# OpenTx_NucleoF412zg.net
KiCad netlist of a schematic drawn in Altium Designer
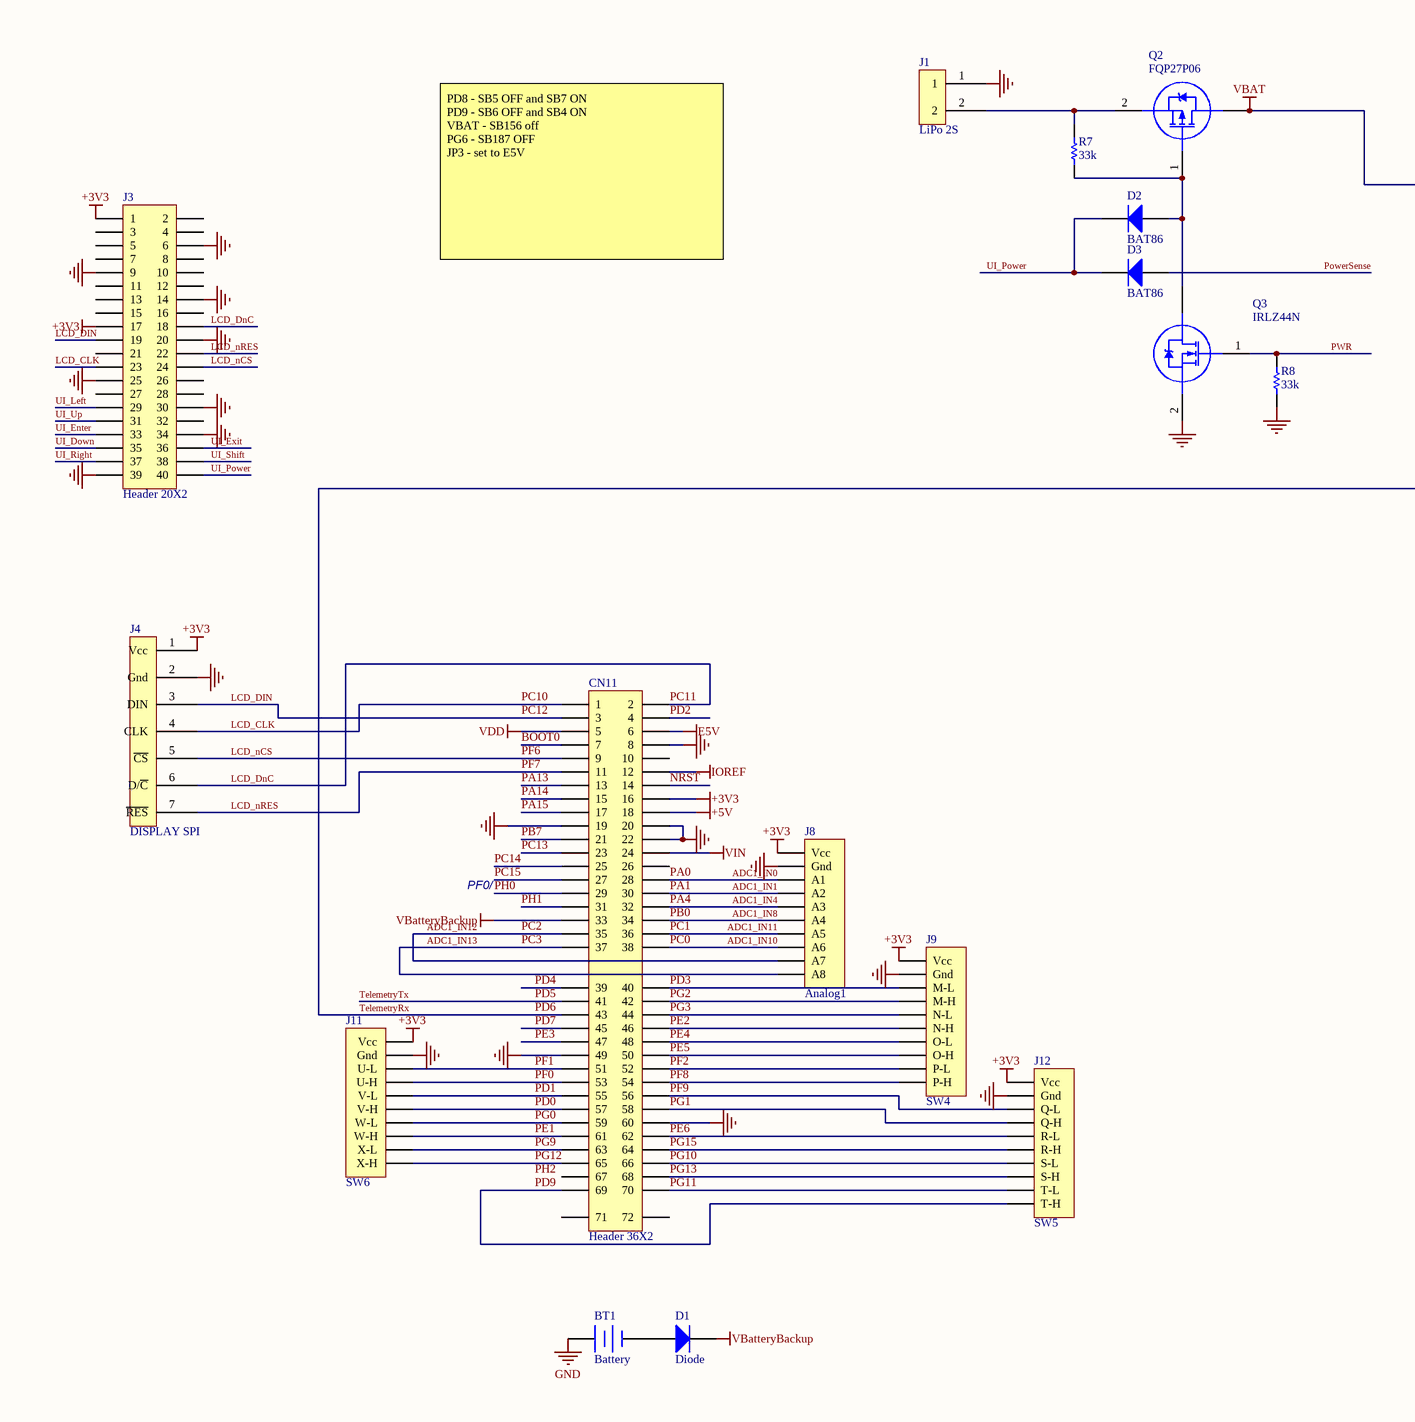
[diagram p0: OpenTx_NucleoF412zg.SchDoc, left]
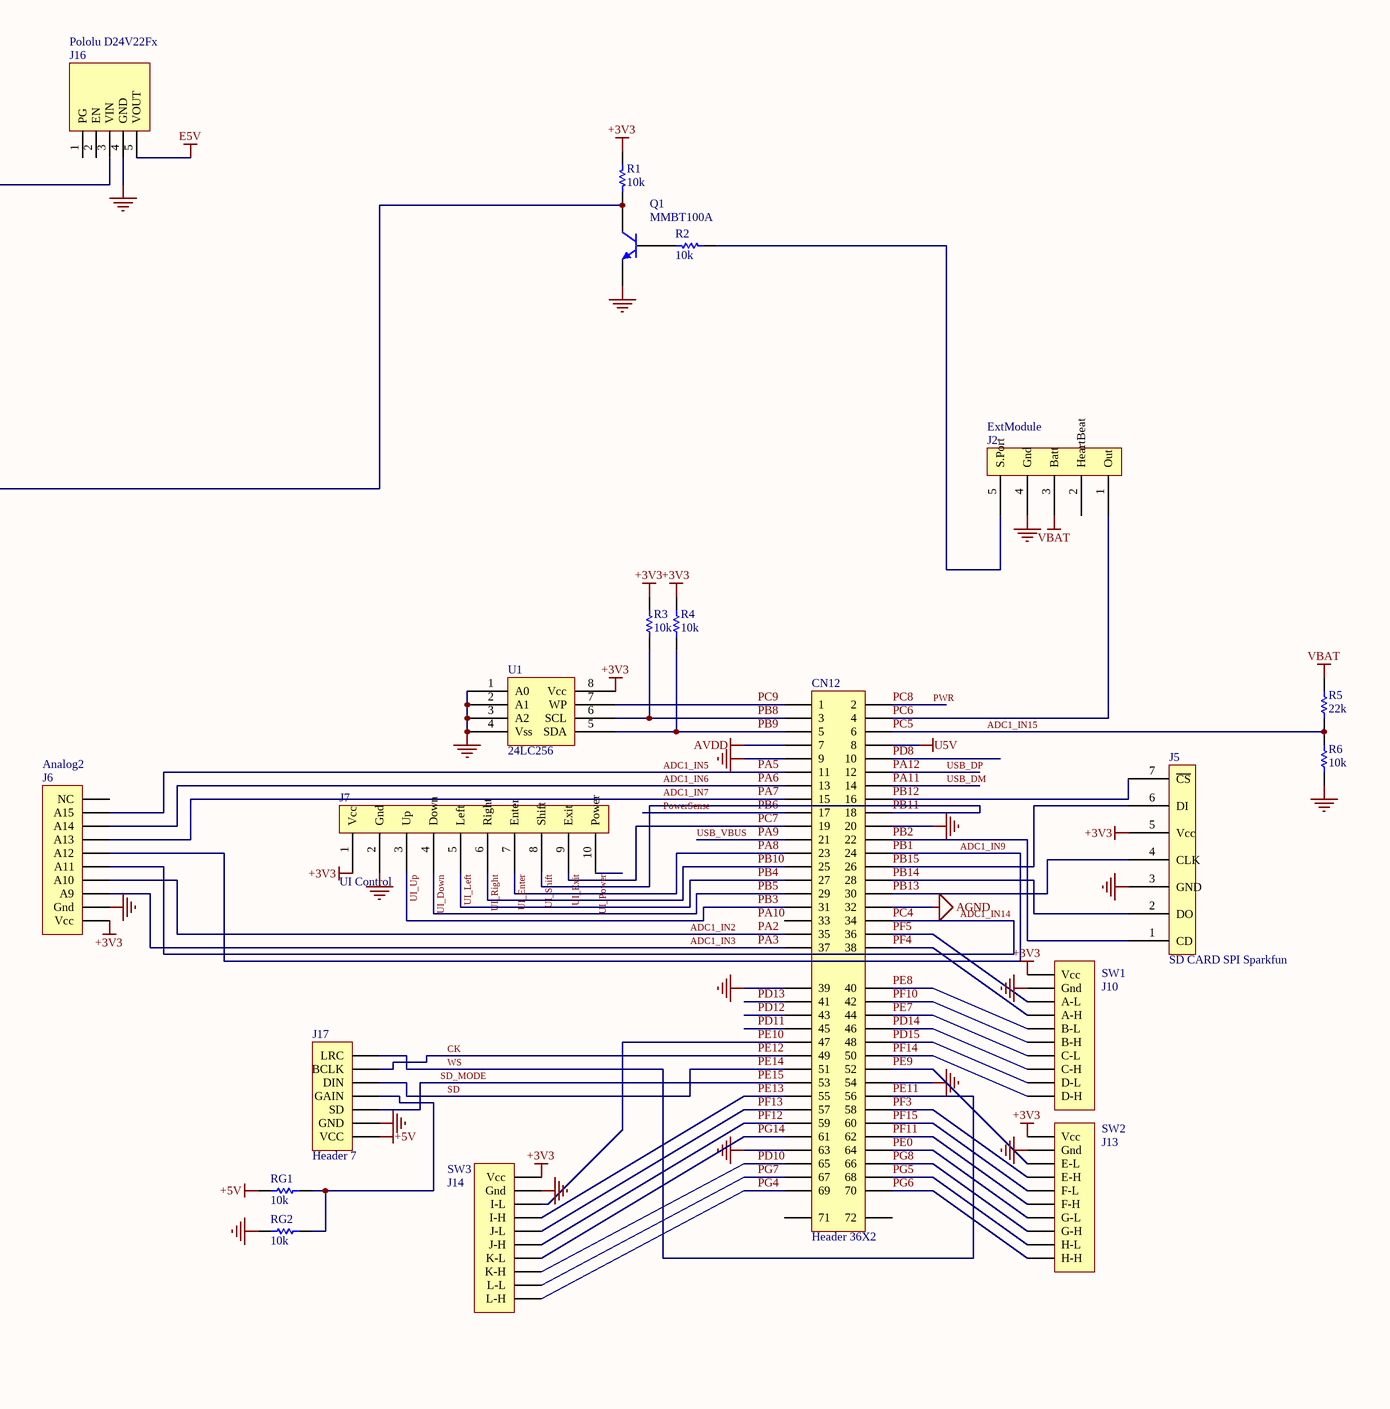
[diagram p1: OpenTx_NucleoF412zg.SchDoc, right]

(export (version "E")
  (design (tool "Eeschema 10.0.6"))
  (components
    (comp (ref "BT1")
      (value "Battery")
      (footprint "Button Cell Holder 20mm")
      (description "Multicell Battery")
      (fields (field (name "PUBLISHER") "Altium Limited"))
      (libsource (lib "Miscellaneous Devices") (part "Battery"))
    )
    (comp (ref "CN11")
      (value "Header 36X2")
      (footprint "HDR35x2 Bottom")
      (description "Header, 36-Pin, Dual row")
      (fields (field (name "PUBLISHER") "Altium Limited"))
      (libsource (lib "MB1137") (part "Header 36X2"))
    )
    (comp (ref "CN12")
      (value "Header 36X2")
      (footprint "HDR35x2 Bottom")
      (description "Header, 36-Pin, Dual row")
      (fields (field (name "PUBLISHER") "Altium Limited"))
      (libsource (lib "MB1137") (part "Header 36X2"))
    )
    (comp (ref "D1")
      (value "Diode")
      (footprint "DO-35 400")
      (fields (field (name "PUBLISHER") "Altium Limited"))
      (libsource (lib "Custom") (part "Diode"))
    )
    (comp (ref "D2")
      (value "BAT86")
      (footprint "DO-35 200")
      (description "Diode")
      (fields (field (name "PUBLISHER") "Altium Limited"))
      (libsource (lib "Custom") (part "Diode"))
    )
    (comp (ref "D3")
      (value "BAT86")
      (footprint "DO-35 200")
      (description "Diode")
      (fields (field (name "PUBLISHER") "Altium Limited"))
      (libsource (lib "Custom") (part "Diode"))
    )
    (comp (ref "J1")
      (value "LiPo 2S")
      (footprint "0.1 SIP 2 PIN")
      (libsource (lib "Custom") (part "SIP2 CONNECTOR"))
    )
    (comp (ref "J2")
      (value "ExtModule")
      (footprint "0.1 SIP 5 PIN")
      (libsource (lib "Custom") (part "SIP5 CONNECTOR"))
    )
    (comp (ref "J3")
      (value "Header 20X2")
      (footprint "HDR20x2 Shrouded")
      (description "Header, 20-Pin, Dual row")
      (fields (field (name "PUBLISHER") "Altium Limited"))
      (libsource (lib "Miscellaneous Connectors") (part "Header 20X2"))
    )
    (comp (ref "J4")
      (value "DISPLAY SPI")
      (footprint "0.1 SIP 8 PIN")
      (libsource (lib "") (part "SIP7 CONNECTOR_1"))
    )
    (comp (ref "J5")
      (value "SD CARD SPI Sparkfun")
      (footprint "Sparkfun SD Card")
      (libsource (lib "Custom") (part "SIP7 CONNECTOR"))
    )
    (comp (ref "J6")
      (value "Analog2")
      (footprint "0.1 SIP 10 PIN")
      (description "Header, 10-Pin")
      (fields (field (name "PUBLISHER") "Altium Limited"))
      (libsource (lib "") (part "Header 10_6"))
    )
    (comp (ref "J7")
      (value "UI Control")
      (footprint "0.1 SIP 10 PIN")
      (libsource (lib "Custom") (part "SIP10 CONNECTOR"))
    )
    (comp (ref "J8")
      (value "Analog1")
      (footprint "0.1 SIP 10 PIN")
      (description "Header, 10-Pin")
      (fields (field (name "PUBLISHER") "Altium Limited"))
      (libsource (lib "") (part "Header 10_2"))
    )
    (comp (ref "J9")
      (value "SW4")
      (footprint "0.1 SIP 10 PIN")
      (description "Header, 10-Pin")
      (fields (field (name "PUBLISHER") "Altium Limited"))
      (libsource (lib "") (part "Header 10_4"))
    )
    (comp (ref "J10")
      (value "SW1")
      (footprint "0.1 SIP 10 PIN")
      (description "Header, 10-Pin")
      (fields (field (name "PUBLISHER") "Altium Limited"))
      (libsource (lib "") (part "Header 10_3"))
    )
    (comp (ref "J11")
      (value "SW6")
      (footprint "0.1 SIP 10 PIN")
      (description "Header, 10-Pin")
      (fields (field (name "PUBLISHER") "Altium Limited"))
      (libsource (lib "") (part "Header 10_1"))
    )
    (comp (ref "J12")
      (value "SW5")
      (footprint "0.1 SIP 10 PIN")
      (description "Header, 10-Pin")
      (fields (field (name "PUBLISHER") "Altium Limited"))
      (libsource (lib "Miscellaneous Connectors") (part "Header 10"))
    )
    (comp (ref "J13")
      (value "SW2")
      (footprint "0.1 SIP 10 PIN")
      (description "Header, 10-Pin")
      (fields (field (name "PUBLISHER") "Altium Limited"))
      (libsource (lib "") (part "Header 10_5"))
    )
    (comp (ref "J14")
      (value "SW3")
      (footprint "0.1 SIP 10 PIN")
      (description "Header, 10-Pin")
      (fields (field (name "PUBLISHER") "Altium Limited"))
      (libsource (lib "") (part "Header 10_1"))
    )
    (comp (ref "J16")
      (value "Pololu D24V22Fx")
      (footprint "Pololu D24V22Fx")
      (libsource (lib "Custom") (part "Pololu D24V22Fx"))
    )
    (comp (ref "J17")
      (value "Header 7")
      (footprint "ADAFruit I2S MAX98357A")
      (description "Header, 7-Pin")
      (fields (field (name "PUBLISHER") "Altium Limited"))
      (libsource (lib "Miscellaneous Connectors") (part "Header 7"))
    )
    (comp (ref "Q1")
      (value "MMBT100A")
      (footprint "TO-92 0.1\"")
      (description "General Purpose Amplifier NPN Silicon")
      (fields (field (name "PUBLISHER") "Altium Limited"))
      (libsource (lib "Custom") (part "MMBT100A"))
    )
    (comp (ref "Q2")
      (value "FQP27P06")
      (footprint "TO-220")
      (description "HEXFET Power MOSFET")
      (fields (field (name "PUBLISHER") "Altium Limited"))
      (libsource (lib "Custom") (part "NTR4101P"))
    )
    (comp (ref "Q3")
      (value "IRLZ44N")
      (footprint "TO-220")
      (description "HEXFET Power MOSFET")
      (fields (field (name "PUBLISHER") "Altium Limited"))
      (libsource (lib "Custom") (part "NTR4501N"))
    )
    (comp (ref "R1")
      (value "10k")
      (footprint "Resistor Axial 1/8W 0.4")
      (fields (field (name "Comment") "Res1"))
      (libsource (lib "Custom") (part "Resistor"))
    )
    (comp (ref "R2")
      (value "10k")
      (footprint "Resistor Axial 1/8W 0.4")
      (fields (field (name "Comment") "Res1"))
      (libsource (lib "Custom") (part "Resistor"))
    )
    (comp (ref "R3")
      (value "10k")
      (footprint "Resistor Axial 1/8W 0.4")
      (fields (field (name "Comment") "Res1"))
      (libsource (lib "Custom") (part "Resistor"))
    )
    (comp (ref "R4")
      (value "10k")
      (footprint "Resistor Axial 1/8W 0.4")
      (fields (field (name "Comment") "Res1"))
      (libsource (lib "Custom") (part "Resistor"))
    )
    (comp (ref "R5")
      (value "22k")
      (footprint "Resistor Axial 1/8W 0.4")
      (fields (field (name "Comment") "Res1"))
      (libsource (lib "Custom") (part "Resistor"))
    )
    (comp (ref "R6")
      (value "10k")
      (footprint "Resistor Axial 1/8W 0.4")
      (fields (field (name "Comment") "Res1"))
      (libsource (lib "Custom") (part "Resistor"))
    )
    (comp (ref "R7")
      (value "33k")
      (footprint "Resistor Axial 1/8W 0.4")
      (fields (field (name "Comment") "Res1"))
      (libsource (lib "Custom") (part "Resistor"))
    )
    (comp (ref "R8")
      (value "33k")
      (footprint "Resistor Axial 1/8W 0.4")
      (fields (field (name "Comment") "Res1"))
      (libsource (lib "Custom") (part "Resistor"))
    )
    (comp (ref "RG1")
      (value "10k")
      (footprint "Resistor Axial 1/8W 0.4")
      (fields (field (name "Comment") "Res1"))
      (libsource (lib "Custom") (part "Resistor"))
    )
    (comp (ref "RG2")
      (value "10k")
      (footprint "Resistor Axial 1/8W 0.4")
      (fields (field (name "Comment") "Res1"))
      (libsource (lib "Custom") (part "Resistor"))
    )
    (comp (ref "U1") (value "24LC256") (footprint "DIP8") (libsource (lib "Custom") (part "24LC256")))
  )
  (nets
    (net (code "1") (name "+3V3") (class "Default")
      (node (ref "CN11") (pin "16") (pinfunction "16_16") (pintype "passive"))
      (node (ref "J10") (pin "1") (pinfunction "Vcc_1") (pintype "passive"))
      (node (ref "J11") (pin "1") (pinfunction "Vcc_1") (pintype "passive"))
      (node (ref "J12") (pin "1") (pinfunction "Vcc_1") (pintype "passive"))
      (node (ref "J13") (pin "1") (pinfunction "Vcc_1") (pintype "passive"))
      (node (ref "J14") (pin "1") (pinfunction "Vcc_1") (pintype "passive"))
      (node (ref "J3") (pin "1") (pinfunction "1_1") (pintype "passive"))
      (node (ref "J3") (pin "17") (pinfunction "17_17") (pintype "passive"))
      (node (ref "J4") (pin "1") (pinfunction "Vcc_1") (pintype "passive"))
      (node (ref "J5") (pin "5") (pinfunction "Vcc_5") (pintype "passive"))
      (node (ref "J6") (pin "1") (pinfunction "Vcc_1") (pintype "passive"))
      (node (ref "J7") (pin "1") (pinfunction "Vcc_1") (pintype "passive"))
      (node (ref "J8") (pin "1") (pinfunction "Vcc_1") (pintype "passive"))
      (node (ref "J9") (pin "1") (pinfunction "Vcc_1") (pintype "passive"))
      (node (ref "R1") (pin "1") (pinfunction "1_1") (pintype "passive"))
      (node (ref "R3") (pin "1") (pinfunction "1_1") (pintype "passive"))
      (node (ref "R4") (pin "1") (pinfunction "1_1") (pintype "passive"))
      (node (ref "U1") (pin "8") (pinfunction "Vcc_8") (pintype "passive"))
    )
    (net (code "2") (name "+5V") (class "Default")
      (node (ref "CN11") (pin "18") (pinfunction "18_18") (pintype "passive"))
      (node (ref "J17") (pin "7") (pinfunction "VCC_7") (pintype "passive"))
      (node (ref "RG1") (pin "1") (pinfunction "1_1") (pintype "passive"))
    )
    (net (code "3") (name "/ADC1_IN0") (class "Default")
      (node (ref "CN11") (pin "28") (pinfunction "28_28") (pintype "passive"))
      (node (ref "J8") (pin "3") (pinfunction "A1_3") (pintype "passive"))
    )
    (net (code "4") (name "/ADC1_IN1") (class "Default")
      (node (ref "CN11") (pin "30") (pinfunction "30_30") (pintype "passive"))
      (node (ref "J8") (pin "4") (pinfunction "A2_4") (pintype "passive"))
    )
    (net (code "5") (name "/ADC1_IN2") (class "Default")
      (node (ref "CN12") (pin "35") (pinfunction "35_35") (pintype "passive"))
      (node (ref "J6") (pin "4") (pinfunction "A10_4") (pintype "passive"))
    )
    (net (code "6") (name "/ADC1_IN3") (class "Default")
      (node (ref "CN12") (pin "37") (pinfunction "37_37") (pintype "passive"))
      (node (ref "J6") (pin "3") (pinfunction "A9_3") (pintype "passive"))
    )
    (net (code "7") (name "/ADC1_IN4") (class "Default")
      (node (ref "CN11") (pin "32") (pinfunction "32_32") (pintype "passive"))
      (node (ref "J8") (pin "5") (pinfunction "A3_5") (pintype "passive"))
    )
    (net (code "8") (name "/ADC1_IN5") (class "Default")
      (node (ref "CN12") (pin "11") (pinfunction "11_11") (pintype "passive"))
      (node (ref "J6") (pin "9") (pinfunction "A15_9") (pintype "passive"))
    )
    (net (code "9") (name "/ADC1_IN6") (class "Default")
      (node (ref "CN12") (pin "13") (pinfunction "13_13") (pintype "passive"))
      (node (ref "J6") (pin "8") (pinfunction "A14_8") (pintype "passive"))
    )
    (net (code "10") (name "/ADC1_IN7") (class "Default")
      (node (ref "CN12") (pin "15") (pinfunction "15_15") (pintype "passive"))
      (node (ref "J6") (pin "7") (pinfunction "A13_7") (pintype "passive"))
    )
    (net (code "11") (name "/ADC1_IN8") (class "Default")
      (node (ref "CN11") (pin "34") (pinfunction "34_34") (pintype "passive"))
      (node (ref "J8") (pin "6") (pinfunction "A4_6") (pintype "passive"))
    )
    (net (code "12") (name "/ADC1_IN9") (class "Default")
      (node (ref "CN12") (pin "24") (pinfunction "24_24") (pintype "passive"))
      (node (ref "J6") (pin "6") (pinfunction "A12_6") (pintype "passive"))
    )
    (net (code "13") (name "/ADC1_IN10") (class "Default")
      (node (ref "CN11") (pin "38") (pinfunction "38_38") (pintype "passive"))
      (node (ref "J8") (pin "8") (pinfunction "A6_8") (pintype "passive"))
    )
    (net (code "14") (name "/ADC1_IN11") (class "Default")
      (node (ref "CN11") (pin "36") (pinfunction "36_36") (pintype "passive"))
      (node (ref "J8") (pin "7") (pinfunction "A5_7") (pintype "passive"))
    )
    (net (code "15") (name "/ADC1_IN12") (class "Default")
      (node (ref "CN11") (pin "35") (pinfunction "35_35") (pintype "passive"))
      (node (ref "J8") (pin "9") (pinfunction "A7_9") (pintype "passive"))
    )
    (net (code "16") (name "/ADC1_IN13") (class "Default")
      (node (ref "CN11") (pin "37") (pinfunction "37_37") (pintype "passive"))
      (node (ref "J8") (pin "10") (pinfunction "A8_10") (pintype "passive"))
    )
    (net (code "17") (name "/ADC1_IN14") (class "Default")
      (node (ref "CN12") (pin "34") (pinfunction "34_34") (pintype "passive"))
      (node (ref "J6") (pin "5") (pinfunction "A11_5") (pintype "passive"))
    )
    (net (code "18") (name "/ADC1_IN15") (class "Default")
      (node (ref "CN12") (pin "6") (pinfunction "6_6") (pintype "passive"))
      (node (ref "R5") (pin "2") (pinfunction "2_2") (pintype "passive"))
      (node (ref "R6") (pin "1") (pinfunction "1_1") (pintype "passive"))
    )
    (net (code "19") (name "/BOOT0") (class "Default")
      (node (ref "CN11") (pin "7") (pinfunction "7_7") (pintype "passive"))
    )
    (net (code "20") (name "/CK") (class "Default")
      (node (ref "CN12") (pin "49") (pinfunction "49_49") (pintype "passive"))
      (node (ref "J17") (pin "2") (pinfunction "BCLK_2") (pintype "passive"))
    )
    (net (code "21") (name "/LCD_CLK") (class "Default")
      (node (ref "CN11") (pin "1") (pinfunction "1_1") (pintype "passive"))
      (node (ref "J3") (pin "23") (pinfunction "23_23") (pintype "passive"))
      (node (ref "J4") (pin "4") (pinfunction "CLK_4") (pintype "passive"))
    )
    (net (code "22") (name "/LCD_DIN") (class "Default")
      (node (ref "CN11") (pin "3") (pinfunction "3_3") (pintype "passive"))
      (node (ref "J3") (pin "19") (pinfunction "19_19") (pintype "passive"))
      (node (ref "J4") (pin "3") (pinfunction "DIN_3") (pintype "passive"))
    )
    (net (code "23") (name "/LCD_DnC") (class "Default")
      (node (ref "CN11") (pin "2") (pinfunction "2_2") (pintype "passive"))
      (node (ref "J3") (pin "18") (pinfunction "18_18") (pintype "passive"))
      (node (ref "J4") (pin "6") (pinfunction "D/~{C}_6") (pintype "passive"))
    )
    (net (code "24") (name "/LCD_nCS") (class "Default")
      (node (ref "CN11") (pin "9") (pinfunction "9_9") (pintype "passive"))
      (node (ref "J3") (pin "24") (pinfunction "24_24") (pintype "passive"))
      (node (ref "J4") (pin "5") (pinfunction "~{CS}_5") (pintype "passive"))
    )
    (net (code "25") (name "/LCD_nRES") (class "Default")
      (node (ref "CN11") (pin "11") (pinfunction "11_11") (pintype "passive"))
      (node (ref "J3") (pin "22") (pinfunction "22_22") (pintype "passive"))
      (node (ref "J4") (pin "7") (pinfunction "~{RES}_7") (pintype "passive"))
    )
    (net (code "26") (name "/NRST") (class "Default")
      (node (ref "CN11") (pin "14") (pinfunction "14_14") (pintype "passive"))
    )
    (net (code "27") (name "/PA8") (class "Default")
      (node (ref "CN12") (pin "23") (pinfunction "23_23") (pintype "passive"))
      (node (ref "J3") (pin "33") (pinfunction "33_33") (pintype "passive"))
      (node (ref "J7") (pin "7") (pinfunction "Enter_7") (pintype "passive"))
    )
    (net (code "28") (name "/PA9") (class "Default")
      (node (ref "CN12") (pin "21") (pinfunction "21_21") (pintype "passive"))
    )
    (net (code "30") (name "/PA11") (class "Default")
      (node (ref "CN12") (pin "14") (pinfunction "14_14") (pintype "passive"))
    )
    (net (code "31") (name "/PA12") (class "Default")
      (node (ref "CN12") (pin "12") (pinfunction "12_12") (pintype "passive"))
    )
    (net (code "32") (name "/PA13") (class "Default")
      (node (ref "CN11") (pin "13") (pinfunction "13_13") (pintype "passive"))
    )
    (net (code "33") (name "/PA14") (class "Default")
      (node (ref "CN11") (pin "15") (pinfunction "15_15") (pintype "passive"))
    )
    (net (code "34") (name "/PA15") (class "Default")
      (node (ref "CN11") (pin "17") (pinfunction "17_17") (pintype "passive"))
    )
    (net (code "35") (name "/PB2") (class "Default")
      (node (ref "CN12") (pin "22") (pinfunction "22_22") (pintype "passive"))
      (node (ref "J5") (pin "1") (pinfunction "CD_1") (pintype "passive"))
    )
    (net (code "36") (name "/PB3") (class "Default")
      (node (ref "CN12") (pin "31") (pinfunction "31_31") (pintype "passive"))
      (node (ref "J3") (pin "31") (pinfunction "31_31") (pintype "passive"))
      (node (ref "J7") (pin "3") (pinfunction "Up_3") (pintype "passive"))
    )
    (net (code "37") (name "/PB4") (class "Default")
      (node (ref "CN12") (pin "27") (pinfunction "27_27") (pintype "passive"))
      (node (ref "J3") (pin "29") (pinfunction "29_29") (pintype "passive"))
      (node (ref "J7") (pin "5") (pinfunction "Left_5") (pintype "passive"))
    )
    (net (code "38") (name "/PB5") (class "Default")
      (node (ref "CN12") (pin "29") (pinfunction "29_29") (pintype "passive"))
      (node (ref "J3") (pin "35") (pinfunction "35_35") (pintype "passive"))
      (node (ref "J7") (pin "4") (pinfunction "Down_4") (pintype "passive"))
    )
    (net (code "39") (name "/PB6") (class "Default")
      (node (ref "CN12") (pin "17") (pinfunction "17_17") (pintype "passive"))
      (node (ref "D3") (pin "1") (pinfunction "A_1") (pintype "passive"))
    )
    (net (code "40") (name "/PB7") (class "Default")
      (node (ref "CN11") (pin "21") (pinfunction "21_21") (pintype "passive"))
    )
    (net (code "41") (name "/PB8") (class "Default")
      (node (ref "CN12") (pin "3") (pinfunction "3_3") (pintype "passive"))
      (node (ref "R3") (pin "2") (pinfunction "2_2") (pintype "passive"))
      (node (ref "U1") (pin "6") (pinfunction "SCL_6") (pintype "passive"))
    )
    (net (code "42") (name "/PB9") (class "Default")
      (node (ref "CN12") (pin "5") (pinfunction "5_5") (pintype "passive"))
      (node (ref "R4") (pin "2") (pinfunction "2_2") (pintype "passive"))
      (node (ref "U1") (pin "5") (pinfunction "SDA_5") (pintype "passive"))
    )
    (net (code "43") (name "/PB10") (class "Default")
      (node (ref "CN12") (pin "25") (pinfunction "25_25") (pintype "passive"))
      (node (ref "J3") (pin "37") (pinfunction "37_37") (pintype "passive"))
      (node (ref "J7") (pin "6") (pinfunction "Right_6") (pintype "passive"))
    )
    (net (code "44") (name "/PB11") (class "Default")
      (node (ref "CN12") (pin "18") (pinfunction "18_18") (pintype "passive"))
      (node (ref "J3") (pin "38") (pinfunction "38_38") (pintype "passive"))
      (node (ref "J7") (pin "8") (pinfunction "Shift_8") (pintype "passive"))
    )
    (net (code "45") (name "/PB12") (class "Default")
      (node (ref "CN12") (pin "16") (pinfunction "16_16") (pintype "passive"))
      (node (ref "J5") (pin "7") (pinfunction "~{CS}_7") (pintype "passive"))
    )
    (net (code "46") (name "/PB13") (class "Default")
      (node (ref "CN12") (pin "30") (pinfunction "30_30") (pintype "passive"))
      (node (ref "J5") (pin "4") (pinfunction "CLK_4") (pintype "passive"))
    )
    (net (code "47") (name "/PB14") (class "Default")
      (node (ref "CN12") (pin "28") (pinfunction "28_28") (pintype "passive"))
      (node (ref "J5") (pin "2") (pinfunction "DO_2") (pintype "passive"))
    )
    (net (code "48") (name "/PB15") (class "Default")
      (node (ref "CN12") (pin "26") (pinfunction "26_26") (pintype "passive"))
      (node (ref "J5") (pin "6") (pinfunction "DI_6") (pintype "passive"))
    )
    (net (code "49") (name "/PC6") (class "Default")
      (node (ref "CN12") (pin "4") (pinfunction "4_4") (pintype "passive"))
      (node (ref "J2") (pin "1") (pinfunction "Out_1") (pintype "passive"))
    )
    (net (code "50") (name "/PC7") (class "Default")
      (node (ref "CN12") (pin "19") (pinfunction "19_19") (pintype "passive"))
      (node (ref "J3") (pin "36") (pinfunction "36_36") (pintype "passive"))
      (node (ref "J7") (pin "9") (pinfunction "Exit_9") (pintype "passive"))
    )
    (net (code "51") (name "/PC8") (class "Default")
      (node (ref "CN12") (pin "2") (pinfunction "2_2") (pintype "passive"))
      (node (ref "Q3") (pin "1") (pinfunction "G_1") (pintype "passive"))
      (node (ref "R8") (pin "1") (pinfunction "1_1") (pintype "passive"))
    )
    (net (code "52") (name "/PC9") (class "Default")
      (node (ref "CN12") (pin "1") (pinfunction "1_1") (pintype "passive"))
      (node (ref "U1") (pin "7") (pinfunction "WP_7") (pintype "passive"))
    )
    (net (code "53") (name "/PC13") (class "Default")
      (node (ref "CN11") (pin "23") (pinfunction "23_23") (pintype "passive"))
    )
    (net (code "54") (name "/PC14") (class "Default")
      (node (ref "CN11") (pin "25") (pinfunction "25_25") (pintype "passive"))
    )
    (net (code "55") (name "/PC15") (class "Default")
      (node (ref "CN11") (pin "27") (pinfunction "27_27") (pintype "passive"))
    )
    (net (code "56") (name "/PD0") (class "Default")
      (node (ref "CN11") (pin "57") (pinfunction "57_57") (pintype "passive"))
      (node (ref "J11") (pin "6") (pinfunction "J-H_6") (pintype "passive"))
    )
    (net (code "57") (name "/PD1") (class "Default")
      (node (ref "CN11") (pin "55") (pinfunction "55_55") (pintype "passive"))
      (node (ref "J11") (pin "5") (pinfunction "J-L_5") (pintype "passive"))
    )
    (net (code "58") (name "/PD2") (class "Default")
      (node (ref "CN11") (pin "4") (pinfunction "4_4") (pintype "passive"))
    )
    (net (code "59") (name "/PD3") (class "Default")
      (node (ref "CN11") (pin "40") (pinfunction "40_40") (pintype "passive"))
      (node (ref "J9") (pin "3") (pinfunction "M-L_3") (pintype "passive"))
    )
    (net (code "60") (name "/PD4") (class "Default")
      (node (ref "CN11") (pin "39") (pinfunction "39_39") (pintype "passive"))
    )
    (net (code "61") (name "/PD5") (class "Default")
      (node (ref "CN11") (pin "41") (pinfunction "41_41") (pintype "passive"))
    )
    (net (code "62") (name "/PD6") (class "Default")
      (node (ref "CN11") (pin "43") (pinfunction "43_43") (pintype "passive"))
      (node (ref "Q1") (pin "C") (pinfunction "C_C") (pintype "passive"))
      (node (ref "R1") (pin "2") (pinfunction "2_2") (pintype "passive"))
    )
    (net (code "63") (name "/PD7") (class "Default")
      (node (ref "CN11") (pin "45") (pinfunction "45_45") (pintype "passive"))
    )
    (net (code "64") (name "/PD8") (class "Default")
      (node (ref "CN12") (pin "10") (pinfunction "10_10") (pintype "passive"))
    )
    (net (code "65") (name "/PD9") (class "Default")
      (node (ref "CN11") (pin "69") (pinfunction "69_69") (pintype "passive"))
      (node (ref "J12") (pin "10") (pinfunction "T-H_10") (pintype "passive"))
    )
    (net (code "66") (name "/PD10") (class "Default")
      (node (ref "CN12") (pin "65") (pinfunction "65_65") (pintype "passive"))
      (node (ref "J14") (pin "8") (pinfunction "K-H_8") (pintype "passive"))
    )
    (net (code "67") (name "/PD11") (class "Default")
      (node (ref "CN12") (pin "45") (pinfunction "45_45") (pintype "passive"))
    )
    (net (code "68") (name "/PD12") (class "Default")
      (node (ref "CN12") (pin "43") (pinfunction "43_43") (pintype "passive"))
    )
    (net (code "69") (name "/PD13") (class "Default")
      (node (ref "CN12") (pin "41") (pinfunction "41_41") (pintype "passive"))
    )
    (net (code "70") (name "/PD14") (class "Default")
      (node (ref "CN12") (pin "46") (pinfunction "46_46") (pintype "passive"))
      (node (ref "J10") (pin "8") (pinfunction "C-H_8") (pintype "passive"))
    )
    (net (code "71") (name "/PD15") (class "Default")
      (node (ref "CN12") (pin "48") (pinfunction "48_48") (pintype "passive"))
      (node (ref "J10") (pin "9") (pinfunction "D-L_9") (pintype "passive"))
    )
    (net (code "72") (name "/PE0") (class "Default")
      (node (ref "CN12") (pin "64") (pinfunction "64_64") (pintype "passive"))
      (node (ref "J13") (pin "7") (pinfunction "G-L_7") (pintype "passive"))
    )
    (net (code "73") (name "/PE1") (class "Default")
      (node (ref "CN11") (pin "61") (pinfunction "61_61") (pintype "passive"))
      (node (ref "J11") (pin "8") (pinfunction "K-H_8") (pintype "passive"))
    )
    (net (code "74") (name "/PE2") (class "Default")
      (node (ref "CN11") (pin "46") (pinfunction "46_46") (pintype "passive"))
      (node (ref "J9") (pin "6") (pinfunction "N-H_6") (pintype "passive"))
    )
    (net (code "75") (name "/PE3") (class "Default")
      (node (ref "CN11") (pin "47") (pinfunction "47_47") (pintype "passive"))
    )
    (net (code "76") (name "/PE4") (class "Default")
      (node (ref "CN11") (pin "48") (pinfunction "48_48") (pintype "passive"))
      (node (ref "J9") (pin "7") (pinfunction "O-L_7") (pintype "passive"))
    )
    (net (code "77") (name "/PE5") (class "Default")
      (node (ref "CN11") (pin "50") (pinfunction "50_50") (pintype "passive"))
      (node (ref "J9") (pin "8") (pinfunction "O-H_8") (pintype "passive"))
    )
    (net (code "78") (name "/PE6") (class "Default")
      (node (ref "CN11") (pin "62") (pinfunction "62_62") (pintype "passive"))
      (node (ref "J12") (pin "5") (pinfunction "R-L_5") (pintype "passive"))
    )
    (net (code "79") (name "/PE7") (class "Default")
      (node (ref "CN12") (pin "44") (pinfunction "44_44") (pintype "passive"))
      (node (ref "J10") (pin "7") (pinfunction "C-L_7") (pintype "passive"))
    )
    (net (code "80") (name "/PE8") (class "Default")
      (node (ref "CN12") (pin "40") (pinfunction "40_40") (pintype "passive"))
      (node (ref "J10") (pin "5") (pinfunction "B-L_5") (pintype "passive"))
    )
    (net (code "81") (name "/PE9") (class "Default")
      (node (ref "CN12") (pin "52") (pinfunction "52_52") (pintype "passive"))
      (node (ref "J13") (pin "3") (pinfunction "E-L_3") (pintype "passive"))
    )
    (net (code "82") (name "/PE10") (class "Default")
      (node (ref "CN12") (pin "47") (pinfunction "47_47") (pintype "passive"))
      (node (ref "J14") (pin "3") (pinfunction "I-L_3") (pintype "passive"))
    )
    (net (code "83") (name "/PE11") (class "Default")
      (node (ref "CN12") (pin "56") (pinfunction "56_56") (pintype "passive"))
      (node (ref "J17") (pin "1") (pinfunction "LRC_1") (pintype "passive"))
    )
    (net (code "84") (name "/PE13") (class "Default")
      (node (ref "CN12") (pin "55") (pinfunction "55_55") (pintype "passive"))
      (node (ref "J14") (pin "4") (pinfunction "I-H_4") (pintype "passive"))
    )
    (net (code "85") (name "/PE14") (class "Default")
      (node (ref "CN12") (pin "51") (pinfunction "51_51") (pintype "passive"))
      (node (ref "J17") (pin "3") (pinfunction "DIN_3") (pintype "passive"))
    )
    (net (code "86") (name "/PE15") (class "Default")
      (node (ref "CN12") (pin "53") (pinfunction "53_53") (pintype "passive"))
      (node (ref "J17") (pin "5") (pinfunction "SD_5") (pintype "passive"))
    )
    (net (code "87") (name "/PF0") (class "Default")
      (node (ref "CN11") (pin "53") (pinfunction "53_53") (pintype "passive"))
      (node (ref "J11") (pin "4") (pinfunction "I-H_4") (pintype "passive"))
    )
    (net (code "88") (name "/PF1") (class "Default")
      (node (ref "CN11") (pin "51") (pinfunction "51_51") (pintype "passive"))
      (node (ref "J11") (pin "3") (pinfunction "I-L_3") (pintype "passive"))
    )
    (net (code "89") (name "/PF2") (class "Default")
      (node (ref "CN11") (pin "52") (pinfunction "52_52") (pintype "passive"))
      (node (ref "J9") (pin "9") (pinfunction "P-L_9") (pintype "passive"))
    )
    (net (code "90") (name "/PF3") (class "Default")
      (node (ref "CN12") (pin "58") (pinfunction "58_58") (pintype "passive"))
      (node (ref "J13") (pin "4") (pinfunction "E-H_4") (pintype "passive"))
    )
    (net (code "91") (name "/PF4") (class "Default")
      (node (ref "CN12") (pin "38") (pinfunction "38_38") (pintype "passive"))
      (node (ref "J10") (pin "4") (pinfunction "A-H_4") (pintype "passive"))
    )
    (net (code "92") (name "/PF5") (class "Default")
      (node (ref "CN12") (pin "36") (pinfunction "36_36") (pintype "passive"))
      (node (ref "J10") (pin "3") (pinfunction "A-L_3") (pintype "passive"))
    )
    (net (code "93") (name "/PF8") (class "Default")
      (node (ref "CN11") (pin "54") (pinfunction "54_54") (pintype "passive"))
      (node (ref "J9") (pin "10") (pinfunction "P-H_10") (pintype "passive"))
    )
    (net (code "94") (name "/PF9") (class "Default")
      (node (ref "CN11") (pin "56") (pinfunction "56_56") (pintype "passive"))
      (node (ref "J12") (pin "3") (pinfunction "Q-L_3") (pintype "passive"))
    )
    (net (code "95") (name "/PF10") (class "Default")
      (node (ref "CN12") (pin "42") (pinfunction "42_42") (pintype "passive"))
      (node (ref "J10") (pin "6") (pinfunction "B-H_6") (pintype "passive"))
    )
    (net (code "96") (name "/PF11") (class "Default")
      (node (ref "CN12") (pin "62") (pinfunction "62_62") (pintype "passive"))
      (node (ref "J13") (pin "6") (pinfunction "F-H_6") (pintype "passive"))
    )
    (net (code "97") (name "/PF12") (class "Default")
      (node (ref "CN12") (pin "59") (pinfunction "59_59") (pintype "passive"))
      (node (ref "J14") (pin "6") (pinfunction "J-H_6") (pintype "passive"))
    )
    (net (code "98") (name "/PF13") (class "Default")
      (node (ref "CN12") (pin "57") (pinfunction "57_57") (pintype "passive"))
      (node (ref "J14") (pin "5") (pinfunction "J-L_5") (pintype "passive"))
    )
    (net (code "99") (name "/PF14") (class "Default")
      (node (ref "CN12") (pin "50") (pinfunction "50_50") (pintype "passive"))
      (node (ref "J10") (pin "10") (pinfunction "D-H_10") (pintype "passive"))
    )
    (net (code "100") (name "/PF15") (class "Default")
      (node (ref "CN12") (pin "60") (pinfunction "60_60") (pintype "passive"))
      (node (ref "J13") (pin "5") (pinfunction "F-L_5") (pintype "passive"))
    )
    (net (code "101") (name "/PG0") (class "Default")
      (node (ref "CN11") (pin "59") (pinfunction "59_59") (pintype "passive"))
      (node (ref "J11") (pin "7") (pinfunction "K-L_7") (pintype "passive"))
    )
    (net (code "102") (name "/PG1") (class "Default")
      (node (ref "CN11") (pin "58") (pinfunction "58_58") (pintype "passive"))
      (node (ref "J12") (pin "4") (pinfunction "Q-H_4") (pintype "passive"))
    )
    (net (code "103") (name "/PG2") (class "Default")
      (node (ref "CN11") (pin "42") (pinfunction "42_42") (pintype "passive"))
      (node (ref "J9") (pin "4") (pinfunction "M-H_4") (pintype "passive"))
    )
    (net (code "104") (name "/PG3") (class "Default")
      (node (ref "CN11") (pin "44") (pinfunction "44_44") (pintype "passive"))
      (node (ref "J9") (pin "5") (pinfunction "N-L_5") (pintype "passive"))
    )
    (net (code "105") (name "/PG4") (class "Default")
      (node (ref "CN12") (pin "69") (pinfunction "69_69") (pintype "passive"))
      (node (ref "J14") (pin "10") (pinfunction "L-H_10") (pintype "passive"))
    )
    (net (code "106") (name "/PG5") (class "Default")
      (node (ref "CN12") (pin "68") (pinfunction "68_68") (pintype "passive"))
      (node (ref "J13") (pin "9") (pinfunction "H-L_9") (pintype "passive"))
    )
    (net (code "107") (name "/PG6") (class "Default")
      (node (ref "CN12") (pin "70") (pinfunction "70_70") (pintype "passive"))
      (node (ref "J13") (pin "10") (pinfunction "H-H_10") (pintype "passive"))
    )
    (net (code "108") (name "/PG7") (class "Default")
      (node (ref "CN12") (pin "67") (pinfunction "67_67") (pintype "passive"))
      (node (ref "J14") (pin "9") (pinfunction "L-L_9") (pintype "passive"))
    )
    (net (code "109") (name "/PG8") (class "Default")
      (node (ref "CN12") (pin "66") (pinfunction "66_66") (pintype "passive"))
      (node (ref "J13") (pin "8") (pinfunction "G-H_8") (pintype "passive"))
    )
    (net (code "110") (name "/PG9") (class "Default")
      (node (ref "CN11") (pin "63") (pinfunction "63_63") (pintype "passive"))
      (node (ref "J11") (pin "9") (pinfunction "L-L_9") (pintype "passive"))
    )
    (net (code "111") (name "/PG10") (class "Default")
      (node (ref "CN11") (pin "66") (pinfunction "66_66") (pintype "passive"))
      (node (ref "J12") (pin "7") (pinfunction "S-L_7") (pintype "passive"))
    )
    (net (code "112") (name "/PG11") (class "Default")
      (node (ref "CN11") (pin "70") (pinfunction "70_70") (pintype "passive"))
      (node (ref "J12") (pin "9") (pinfunction "T-L_9") (pintype "passive"))
    )
    (net (code "113") (name "/PG12") (class "Default")
      (node (ref "CN11") (pin "65") (pinfunction "65_65") (pintype "passive"))
      (node (ref "J11") (pin "10") (pinfunction "L-H_10") (pintype "passive"))
    )
    (net (code "114") (name "/PG13") (class "Default")
      (node (ref "CN11") (pin "68") (pinfunction "68_68") (pintype "passive"))
      (node (ref "J12") (pin "8") (pinfunction "S-H_8") (pintype "passive"))
    )
    (net (code "115") (name "/PG14") (class "Default")
      (node (ref "CN12") (pin "61") (pinfunction "61_61") (pintype "passive"))
      (node (ref "J14") (pin "7") (pinfunction "K-L_7") (pintype "passive"))
    )
    (net (code "116") (name "/PG15") (class "Default")
      (node (ref "CN11") (pin "64") (pinfunction "64_64") (pintype "passive"))
      (node (ref "J12") (pin "6") (pinfunction "R-H_6") (pintype "passive"))
    )
    (net (code "117") (name "/PH0") (class "Default")
      (node (ref "CN11") (pin "29") (pinfunction "29_29") (pintype "passive"))
    )
    (net (code "118") (name "/PH1") (class "Default")
      (node (ref "CN11") (pin "31") (pinfunction "31_31") (pintype "passive"))
    )
    (net (code "120") (name "/UI_Power") (class "Default")
      (node (ref "D2") (pin "2") (pinfunction "K_2") (pintype "passive"))
      (node (ref "D3") (pin "2") (pinfunction "K_2") (pintype "passive"))
      (node (ref "J3") (pin "40") (pinfunction "40_40") (pintype "passive"))
      (node (ref "J7") (pin "10") (pinfunction "Power_10") (pintype "passive"))
    )
    (net (code "121") (name "AGND") (class "Default")
      (node (ref "CN12") (pin "32") (pinfunction "32_32") (pintype "passive"))
    )
    (net (code "122") (name "AVDD") (class "Default")
      (node (ref "CN12") (pin "7") (pinfunction "7_7") (pintype "passive"))
    )
    (net (code "123") (name "E5V") (class "Default")
      (node (ref "CN11") (pin "6") (pinfunction "6_6") (pintype "passive"))
      (node (ref "J16") (pin "5") (pinfunction "VOUT_5") (pintype "passive"))
    )
    (net (code "124") (name "GND") (class "Default")
      (node (ref "BT1") (pin "1") (pinfunction "+_1") (pintype "passive"))
      (node (ref "CN11") (pin "19") (pinfunction "19_19") (pintype "passive"))
      (node (ref "CN11") (pin "20") (pinfunction "20_20") (pintype "passive"))
      (node (ref "CN11") (pin "22") (pinfunction "22_22") (pintype "passive"))
      (node (ref "CN11") (pin "49") (pinfunction "49_49") (pintype "passive"))
      (node (ref "CN11") (pin "60") (pinfunction "60_60") (pintype "passive"))
      (node (ref "CN11") (pin "8") (pinfunction "8_8") (pintype "passive"))
      (node (ref "CN12") (pin "20") (pinfunction "20_20") (pintype "passive"))
      (node (ref "CN12") (pin "39") (pinfunction "39_39") (pintype "passive"))
      (node (ref "CN12") (pin "54") (pinfunction "54_54") (pintype "passive"))
      (node (ref "CN12") (pin "63") (pinfunction "63_63") (pintype "passive"))
      (node (ref "CN12") (pin "9") (pinfunction "9_9") (pintype "passive"))
      (node (ref "J1") (pin "1") (pinfunction "1_1") (pintype "passive"))
      (node (ref "J10") (pin "2") (pinfunction "Gnd_2") (pintype "passive"))
      (node (ref "J11") (pin "2") (pinfunction "Gnd_2") (pintype "passive"))
      (node (ref "J12") (pin "2") (pinfunction "Gnd_2") (pintype "passive"))
      (node (ref "J13") (pin "2") (pinfunction "Gnd_2") (pintype "passive"))
      (node (ref "J14") (pin "2") (pinfunction "Gnd_2") (pintype "passive"))
      (node (ref "J16") (pin "4") (pinfunction "GND_4") (pintype "passive"))
      (node (ref "J17") (pin "6") (pinfunction "GND_6") (pintype "passive"))
      (node (ref "J2") (pin "4") (pinfunction "Gnd_4") (pintype "passive"))
      (node (ref "J3") (pin "14") (pinfunction "14_14") (pintype "passive"))
      (node (ref "J3") (pin "20") (pinfunction "20_20") (pintype "passive"))
      (node (ref "J3") (pin "25") (pinfunction "25_25") (pintype "passive"))
      (node (ref "J3") (pin "30") (pinfunction "30_30") (pintype "passive"))
      (node (ref "J3") (pin "34") (pinfunction "34_34") (pintype "passive"))
      (node (ref "J3") (pin "39") (pinfunction "39_39") (pintype "passive"))
      (node (ref "J3") (pin "6") (pinfunction "6_6") (pintype "passive"))
      (node (ref "J3") (pin "9") (pinfunction "9_9") (pintype "passive"))
      (node (ref "J4") (pin "2") (pinfunction "Gnd_2") (pintype "passive"))
      (node (ref "J5") (pin "3") (pinfunction "GND_3") (pintype "passive"))
      (node (ref "J6") (pin "2") (pinfunction "Gnd_2") (pintype "passive"))
      (node (ref "J7") (pin "2") (pinfunction "Gnd_2") (pintype "passive"))
      (node (ref "J8") (pin "2") (pinfunction "Gnd_2") (pintype "passive"))
      (node (ref "J9") (pin "2") (pinfunction "Gnd_2") (pintype "passive"))
      (node (ref "Q1") (pin "E") (pinfunction "E_E") (pintype "passive"))
      (node (ref "Q3") (pin "2") (pinfunction "S_2") (pintype "passive"))
      (node (ref "R6") (pin "2") (pinfunction "2_2") (pintype "passive"))
      (node (ref "R8") (pin "2") (pinfunction "2_2") (pintype "passive"))
      (node (ref "RG2") (pin "1") (pinfunction "1_1") (pintype "passive"))
      (node (ref "U1") (pin "1") (pinfunction "A0_1") (pintype "passive"))
      (node (ref "U1") (pin "2") (pinfunction "A1_2") (pintype "passive"))
      (node (ref "U1") (pin "3") (pinfunction "A2_3") (pintype "passive"))
      (node (ref "U1") (pin "4") (pinfunction "Vss_4") (pintype "passive"))
    )
    (net (code "125") (name "IOREF") (class "Default")
      (node (ref "CN11") (pin "12") (pinfunction "12_12") (pintype "passive"))
    )
    (net (code "126") (name "Net-(BT1--)") (class "Default")
      (node (ref "BT1") (pin "2") (pinfunction "-_2") (pintype "passive"))
      (node (ref "D1") (pin "1") (pinfunction "A_1") (pintype "passive"))
    )
    (net (code "127") (name "Net-(D2-A)") (class "Default")
      (node (ref "D2") (pin "1") (pinfunction "A_1") (pintype "passive"))
      (node (ref "Q2") (pin "1") (pinfunction "G_1") (pintype "passive"))
      (node (ref "Q3") (pin "3") (pinfunction "D_3") (pintype "passive"))
      (node (ref "R7") (pin "2") (pinfunction "2_2") (pintype "passive"))
    )
    (net (code "128") (name "Net-(J2-S.Port)") (class "Default")
      (node (ref "J2") (pin "5") (pinfunction "S.Port_5") (pintype "passive"))
      (node (ref "R2") (pin "1") (pinfunction "1_1") (pintype "passive"))
    )
    (net (code "129") (name "Net-(J17-GAIN)") (class "Default")
      (node (ref "J17") (pin "4") (pinfunction "GAIN_4") (pintype "passive"))
      (node (ref "RG1") (pin "2") (pinfunction "2_2") (pintype "passive"))
      (node (ref "RG2") (pin "2") (pinfunction "2_2") (pintype "passive"))
    )
    (net (code "130") (name "Net-(Q1-PadB)") (class "Default")
      (node (ref "Q1") (pin "B") (pinfunction "B_B") (pintype "passive"))
      (node (ref "R2") (pin "2") (pinfunction "2_2") (pintype "passive"))
    )
    (net (code "131") (name "Net-(Q2-S)") (class "Default")
      (node (ref "J1") (pin "2") (pinfunction "2_2") (pintype "passive"))
      (node (ref "Q2") (pin "2") (pinfunction "S_2") (pintype "passive"))
      (node (ref "R7") (pin "1") (pinfunction "1_1") (pintype "passive"))
    )
    (net (code "132") (name "U5V") (class "Default")
      (node (ref "CN12") (pin "8") (pinfunction "8_8") (pintype "passive"))
    )
    (net (code "133") (name "VBAT") (class "Default")
      (node (ref "J16") (pin "3") (pinfunction "VIN_3") (pintype "passive"))
      (node (ref "J2") (pin "3") (pinfunction "Batt_3") (pintype "passive"))
      (node (ref "Q2") (pin "3") (pinfunction "D_3") (pintype "passive"))
      (node (ref "R5") (pin "1") (pinfunction "1_1") (pintype "passive"))
    )
    (net (code "134") (name "VBatteryBackup") (class "Default")
      (node (ref "CN11") (pin "33") (pinfunction "33_33") (pintype "passive"))
      (node (ref "D1") (pin "2") (pinfunction "K_2") (pintype "passive"))
    )
    (net (code "135") (name "VDD") (class "Default")
      (node (ref "CN11") (pin "5") (pinfunction "5_5") (pintype "passive"))
    )
    (net (code "136") (name "VIN") (class "Default")
      (node (ref "CN11") (pin "24") (pinfunction "24_24") (pintype "passive"))
    )
    (net (code "137") (name "unconnected-(CN11-Pad10)") (class "Default")
      (node (ref "CN11") (pin "10") (pinfunction "10_10") (pintype "passive"))
    )
    (net (code "138") (name "unconnected-(CN11-Pad26)") (class "Default")
      (node (ref "CN11") (pin "26") (pinfunction "26_26") (pintype "passive"))
    )
    (net (code "139") (name "unconnected-(CN11-Pad67)") (class "Default")
      (node (ref "CN11") (pin "67") (pinfunction "67_67") (pintype "passive"))
    )
    (net (code "140") (name "unconnected-(CN11-Pad71)") (class "Default")
      (node (ref "CN11") (pin "71") (pinfunction "71_71") (pintype "passive"))
    )
    (net (code "141") (name "unconnected-(CN11-Pad72)") (class "Default")
      (node (ref "CN11") (pin "72") (pinfunction "72_72") (pintype "passive"))
    )
    (net (code "142") (name "unconnected-(CN12-Pad33)") (class "Default")
      (node (ref "CN12") (pin "33") (pinfunction "33_33") (pintype "passive"))
    )
    (net (code "143") (name "unconnected-(CN12-Pad71)") (class "Default")
      (node (ref "CN12") (pin "71") (pinfunction "71_71") (pintype "passive"))
    )
    (net (code "144") (name "unconnected-(CN12-Pad72)") (class "Default")
      (node (ref "CN12") (pin "72") (pinfunction "72_72") (pintype "passive"))
    )
    (net (code "145") (name "unconnected-(J2-HeartBeat-Pad2)") (class "Default")
      (node (ref "J2") (pin "2") (pinfunction "HeartBeat_2") (pintype "passive"))
    )
    (net (code "146") (name "unconnected-(J3-Pad2)") (class "Default")
      (node (ref "J3") (pin "2") (pinfunction "2_2") (pintype "passive"))
    )
    (net (code "147") (name "unconnected-(J3-Pad3)") (class "Default")
      (node (ref "J3") (pin "3") (pinfunction "3_3") (pintype "passive"))
    )
    (net (code "148") (name "unconnected-(J3-Pad4)") (class "Default")
      (node (ref "J3") (pin "4") (pinfunction "4_4") (pintype "passive"))
    )
    (net (code "149") (name "unconnected-(J3-Pad5)") (class "Default")
      (node (ref "J3") (pin "5") (pinfunction "5_5") (pintype "passive"))
    )
    (net (code "150") (name "unconnected-(J3-Pad7)") (class "Default")
      (node (ref "J3") (pin "7") (pinfunction "7_7") (pintype "passive"))
    )
    (net (code "151") (name "unconnected-(J3-Pad8)") (class "Default")
      (node (ref "J3") (pin "8") (pinfunction "8_8") (pintype "passive"))
    )
    (net (code "152") (name "unconnected-(J3-Pad10)") (class "Default")
      (node (ref "J3") (pin "10") (pinfunction "10_10") (pintype "passive"))
    )
    (net (code "153") (name "unconnected-(J3-Pad11)") (class "Default")
      (node (ref "J3") (pin "11") (pinfunction "11_11") (pintype "passive"))
    )
    (net (code "154") (name "unconnected-(J3-Pad12)") (class "Default")
      (node (ref "J3") (pin "12") (pinfunction "12_12") (pintype "passive"))
    )
    (net (code "155") (name "unconnected-(J3-Pad13)") (class "Default")
      (node (ref "J3") (pin "13") (pinfunction "13_13") (pintype "passive"))
    )
    (net (code "156") (name "unconnected-(J3-Pad15)") (class "Default")
      (node (ref "J3") (pin "15") (pinfunction "15_15") (pintype "passive"))
    )
    (net (code "157") (name "unconnected-(J3-Pad16)") (class "Default")
      (node (ref "J3") (pin "16") (pinfunction "16_16") (pintype "passive"))
    )
    (net (code "158") (name "unconnected-(J3-Pad21)") (class "Default")
      (node (ref "J3") (pin "21") (pinfunction "21_21") (pintype "passive"))
    )
    (net (code "159") (name "unconnected-(J3-Pad26)") (class "Default")
      (node (ref "J3") (pin "26") (pinfunction "26_26") (pintype "passive"))
    )
    (net (code "160") (name "unconnected-(J3-Pad27)") (class "Default")
      (node (ref "J3") (pin "27") (pinfunction "27_27") (pintype "passive"))
    )
    (net (code "161") (name "unconnected-(J3-Pad28)") (class "Default")
      (node (ref "J3") (pin "28") (pinfunction "28_28") (pintype "passive"))
    )
    (net (code "162") (name "unconnected-(J3-Pad32)") (class "Default")
      (node (ref "J3") (pin "32") (pinfunction "32_32") (pintype "passive"))
    )
    (net (code "163") (name "unconnected-(J6-NC-Pad10)") (class "Default")
      (node (ref "J6") (pin "10") (pinfunction "NC_10") (pintype "passive"))
    )
    (net (code "164") (name "unconnected-(J16-EN-Pad2)") (class "Default")
      (node (ref "J16") (pin "2") (pinfunction "EN_2") (pintype "passive"))
    )
    (net (code "165") (name "unconnected-(J16-PG-Pad1)") (class "Default")
      (node (ref "J16") (pin "1") (pinfunction "PG_1") (pintype "passive"))
    )
  )
)
